# module.net
KiCad netlist of a schematic drawn in EAGLE
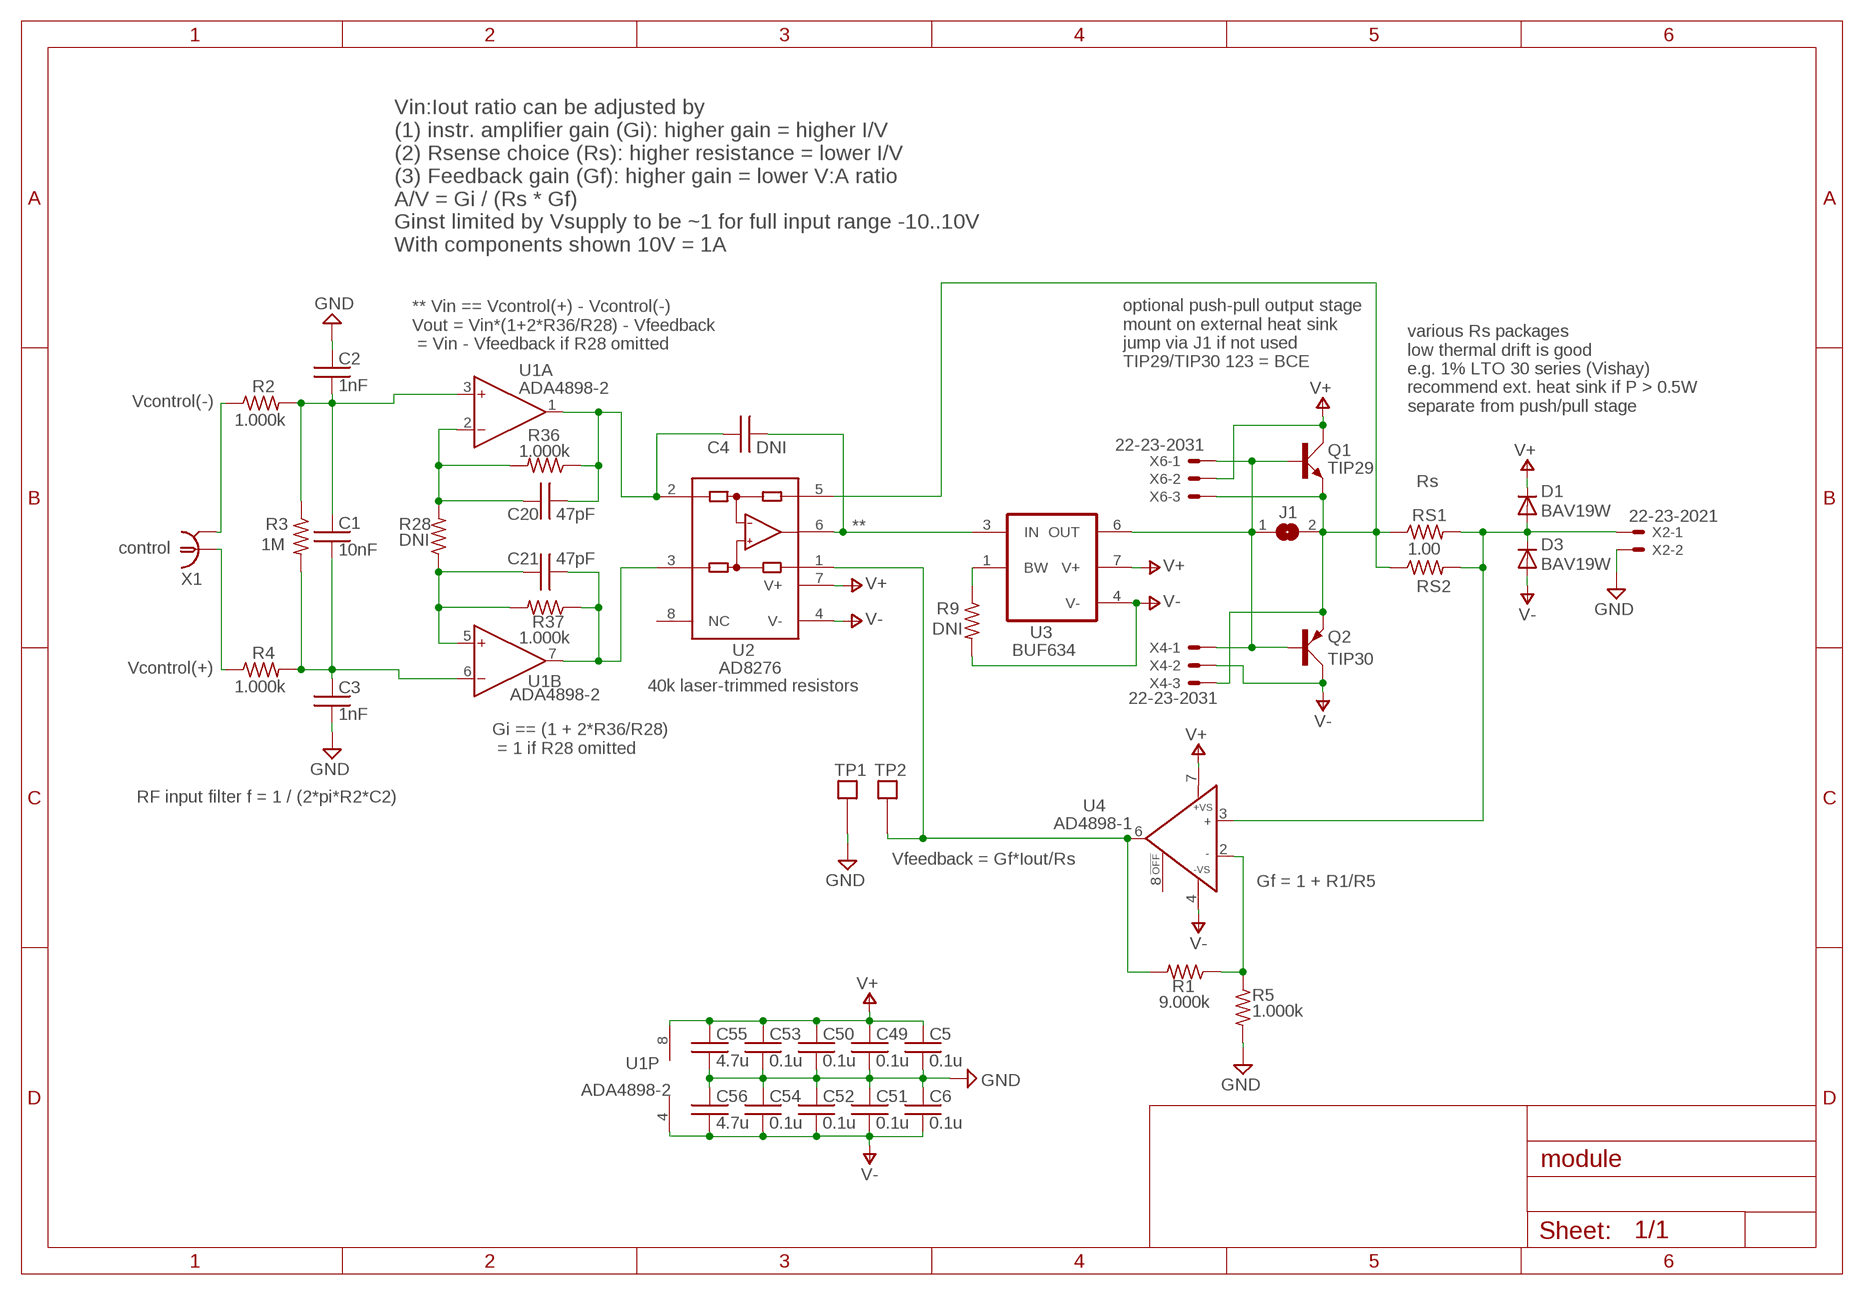
[diagram p0: schematic, sheet 1]

(export (version "E")
  (design (tool "Eeschema 10.0.6"))
  (components
    (comp (ref "C1")
      (value "10nF")
      (footprint "eagle-import:0603")
      (libsource (lib "eagle-import") (part "C0603"))
    )
    (comp (ref "C2")
      (value "1nF")
      (footprint "eagle-import:0603")
      (libsource (lib "eagle-import") (part "C0603"))
    )
    (comp (ref "C3")
      (value "1nF")
      (footprint "eagle-import:0603")
      (libsource (lib "eagle-import") (part "C0603"))
    )
    (comp (ref "C4")
      (value "DNI")
      (footprint "eagle-import:0603")
      (libsource (lib "eagle-import") (part "C0603"))
    )
    (comp (ref "C5")
      (value "0.1u")
      (footprint "eagle-import:0603")
      (libsource (lib "eagle-import") (part "C0603"))
    )
    (comp (ref "C6")
      (value "0.1u")
      (footprint "eagle-import:0603")
      (libsource (lib "eagle-import") (part "C0603"))
    )
    (comp (ref "C20")
      (value "47pF")
      (footprint "eagle-import:0603")
      (libsource (lib "eagle-import") (part "C0603"))
    )
    (comp (ref "C21")
      (value "47pF")
      (footprint "eagle-import:0603")
      (libsource (lib "eagle-import") (part "C0603"))
    )
    (comp (ref "C49")
      (value "0.1u")
      (footprint "eagle-import:0603")
      (libsource (lib "eagle-import") (part "C0603"))
    )
    (comp (ref "C50")
      (value "0.1u")
      (footprint "eagle-import:0603")
      (libsource (lib "eagle-import") (part "C0603"))
    )
    (comp (ref "C51")
      (value "0.1u")
      (footprint "eagle-import:0603")
      (libsource (lib "eagle-import") (part "C0603"))
    )
    (comp (ref "C52")
      (value "0.1u")
      (footprint "eagle-import:0603")
      (libsource (lib "eagle-import") (part "C0603"))
    )
    (comp (ref "C53")
      (value "0.1u")
      (footprint "eagle-import:0603")
      (libsource (lib "eagle-import") (part "C0603"))
    )
    (comp (ref "C54")
      (value "0.1u")
      (footprint "eagle-import:0603")
      (libsource (lib "eagle-import") (part "C0603"))
    )
    (comp (ref "C55")
      (value "4.7u")
      (footprint "eagle-import:0603")
      (libsource (lib "eagle-import") (part "C0603"))
    )
    (comp (ref "C56")
      (value "4.7u")
      (footprint "eagle-import:0603")
      (libsource (lib "eagle-import") (part "C0603"))
    )
    (comp (ref "D1")
      (value "BAV19W")
      (footprint "eagle-import:SOD123")
      (libsource (lib "eagle-import") (part "DIODE-SOD123"))
    )
    (comp (ref "D3")
      (value "BAV19W")
      (footprint "eagle-import:SOD123")
      (libsource (lib "eagle-import") (part "DIODE-SOD123"))
    )
    (comp (ref "J1") (value "SJ") (footprint "eagle-import:SJ") (libsource (lib "eagle-import") (part "SJ")))
    (comp (ref "Q1")
      (value "TIP29")
      (footprint "eagle-import:TO220AV")
      (libsource (lib "eagle-import") (part "TIP41C"))
    )
    (comp (ref "Q2")
      (value "TIP30")
      (footprint "eagle-import:TO220AV")
      (libsource (lib "eagle-import") (part "TIP42C"))
    )
    (comp (ref "R1")
      (value "9.000k")
      (footprint "eagle-import:0603")
      (libsource (lib "eagle-import") (part "R0603"))
    )
    (comp (ref "R2")
      (value "1.000k")
      (footprint "eagle-import:0603")
      (libsource (lib "eagle-import") (part "R0603"))
    )
    (comp (ref "R3")
      (value "1M")
      (footprint "eagle-import:0603")
      (libsource (lib "eagle-import") (part "R0603"))
    )
    (comp (ref "R4")
      (value "1.000k")
      (footprint "eagle-import:0603")
      (libsource (lib "eagle-import") (part "R0603"))
    )
    (comp (ref "R5")
      (value "1.000k")
      (footprint "eagle-import:0603")
      (libsource (lib "eagle-import") (part "R0603"))
    )
    (comp (ref "R9")
      (value "DNI")
      (footprint "eagle-import:0603")
      (libsource (lib "eagle-import") (part "R0603"))
    )
    (comp (ref "R28")
      (value "DNI")
      (footprint "eagle-import:0603")
      (libsource (lib "eagle-import") (part "R0603"))
    )
    (comp (ref "R36")
      (value "1.000k")
      (footprint "eagle-import:0603")
      (libsource (lib "eagle-import") (part "R0603"))
    )
    (comp (ref "R37")
      (value "1.000k")
      (footprint "eagle-import:0603")
      (libsource (lib "eagle-import") (part "R0603"))
    )
    (comp (ref "RS1")
      (value "1.00")
      (footprint "eagle-import:LTO30")
      (libsource (lib "eagle-import") (part "LT030"))
    )
    (comp (ref "RS2")
      (value "DNI")
      (footprint "eagle-import:2512")
      (libsource (lib "eagle-import") (part "RESISTOR2512"))
    )
    (comp (ref "TP1")
      (value "TESTPOINT")
      (footprint "eagle-import:TESTPOINT")
      (libsource (lib "eagle-import") (part "TESTPOINT"))
    )
    (comp (ref "TP2")
      (value "TESTPOINT")
      (footprint "eagle-import:TESTPOINT")
      (libsource (lib "eagle-import") (part "TESTPOINT"))
    )
    (comp (ref "U1")
      (value "ADA4898-2")
      (footprint "eagle-import:SO8")
      (fields (field (name "MF") "ALTERA CORPORATION") (field (name "MPN") "AD8542ARZ-REEL"))
      (libsource (lib "eagle-import") (part "ADA4898-2R"))
    )
    (comp (ref "U2")
      (value "AD8276")
      (footprint "eagle-import:SO8")
      (libsource (lib "eagle-import") (part "AD8276"))
    )
    (comp (ref "U3")
      (value "BUF634")
      (footprint "eagle-import:SO8")
      (libsource (lib "eagle-import") (part "BUF634"))
    )
    (comp (ref "U4")
      (value "AD4898-1")
      (footprint "eagle-import:SO8")
      (fields (field (name "MF") "ANALOG DEVICES") (field (name "MPN") "AD744JR"))
      (libsource (lib "eagle-import") (part "ADA4898-1R"))
    )
    (comp (ref "X1")
      (value "1-227161-0")
      (footprint "eagle-import:AMP_227161")
      (fields (field (name "MF") "TYCO ELECTRONICS") (field (name "MPN") "1-227161"))
      (libsource (lib "eagle-import") (part "?2271611--0"))
    )
    (comp (ref "X2")
      (value "22-23-2021")
      (footprint "eagle-import:22-23-2021")
      (fields (field (name "MF") "MOLEX"))
      (libsource (lib "eagle-import") (part "22-23-2021"))
    )
    (comp (ref "X4")
      (value "22-23-2031")
      (footprint "eagle-import:22-23-2031")
      (fields (field (name "MF") "MOLEX"))
      (libsource (lib "eagle-import") (part "22-23-2031"))
    )
    (comp (ref "X6")
      (value "22-23-2031")
      (footprint "eagle-import:22-23-2031")
      (fields (field (name "MF") "MOLEX"))
      (libsource (lib "eagle-import") (part "22-23-2031"))
    )
  )
  (nets
    (net (code "1") (name "GND") (class "Default")
      (node (ref "C2") (pin "1") (pinfunction "1_1") (pintype "passive"))
      (node (ref "C3") (pin "2") (pinfunction "2_2") (pintype "passive"))
      (node (ref "C49") (pin "2") (pinfunction "2_2") (pintype "passive"))
      (node (ref "C5") (pin "2") (pinfunction "2_2") (pintype "passive"))
      (node (ref "C50") (pin "2") (pinfunction "2_2") (pintype "passive"))
      (node (ref "C51") (pin "1") (pinfunction "1_1") (pintype "passive"))
      (node (ref "C52") (pin "1") (pinfunction "1_1") (pintype "passive"))
      (node (ref "C53") (pin "2") (pinfunction "2_2") (pintype "passive"))
      (node (ref "C54") (pin "1") (pinfunction "1_1") (pintype "passive"))
      (node (ref "C55") (pin "2") (pinfunction "2_2") (pintype "passive"))
      (node (ref "C56") (pin "1") (pinfunction "1_1") (pintype "passive"))
      (node (ref "C6") (pin "1") (pinfunction "1_1") (pintype "passive"))
      (node (ref "R5") (pin "2") (pinfunction "2_2") (pintype "passive"))
      (node (ref "TP1") (pin "P$1") (pinfunction "P$1_P$1") (pintype "bidirectional"))
      (node (ref "X2") (pin "2") (pinfunction "S_2") (pintype "passive"))
    )
    (net (code "2") (name "Net-(R2-Pad1)") (class "Default")
      (node (ref "R2") (pin "1") (pinfunction "1_1") (pintype "passive"))
      (node (ref "X1") (pin "2") (pinfunction "2_2") (pintype "passive"))
    )
    (net (code "3") (name "Net-(R4-Pad1)") (class "Default")
      (node (ref "R4") (pin "1") (pinfunction "1_1") (pintype "passive"))
      (node (ref "X1") (pin "1") (pinfunction "1_1") (pintype "passive"))
    )
    (net (code "4") (name "Net-(RS1-1)") (class "Default")
      (node (ref "J1") (pin "2") (pinfunction "2_2") (pintype "passive"))
      (node (ref "Q1") (pin "E") (pinfunction "E_E") (pintype "passive"))
      (node (ref "Q2") (pin "E") (pinfunction "E_E") (pintype "passive"))
      (node (ref "RS1") (pin "P$1") (pinfunction "1_P$1") (pintype "passive"))
      (node (ref "RS2") (pin "1") (pinfunction "1_1") (pintype "passive"))
      (node (ref "U2") (pin "5") (pinfunction "SENSE_5") (pintype "passive"))
      (node (ref "X4") (pin "3") (pinfunction "S_3") (pintype "passive"))
      (node (ref "X6") (pin "3") (pinfunction "S_3") (pintype "passive"))
    )
    (net (code "5") (name "Net-(RS1-2)") (class "Default")
      (node (ref "D1") (pin "A") (pinfunction "A_A") (pintype "passive"))
      (node (ref "D3") (pin "C") (pinfunction "C_C") (pintype "passive"))
      (node (ref "RS1") (pin "P$2") (pinfunction "2_P$2") (pintype "passive"))
      (node (ref "RS2") (pin "2") (pinfunction "2_2") (pintype "passive"))
      (node (ref "U4") (pin "3") (pinfunction "IN+_3") (pintype "input"))
      (node (ref "X2") (pin "1") (pinfunction "S_1") (pintype "passive"))
    )
    (net (code "6") (name "Net-(U1A-IN+)") (class "Default")
      (node (ref "C1") (pin "1") (pinfunction "1_1") (pintype "passive"))
      (node (ref "C2") (pin "2") (pinfunction "2_2") (pintype "passive"))
      (node (ref "R2") (pin "2") (pinfunction "2_2") (pintype "passive"))
      (node (ref "R3") (pin "1") (pinfunction "1_1") (pintype "passive"))
      (node (ref "U1") (pin "3") (pinfunction "IN+_3") (pintype "input"))
    )
    (net (code "7") (name "Net-(U1A-IN-)") (class "Default")
      (node (ref "C20") (pin "1") (pinfunction "1_1") (pintype "passive"))
      (node (ref "R28") (pin "2") (pinfunction "2_2") (pintype "passive"))
      (node (ref "R36") (pin "2") (pinfunction "2_2") (pintype "passive"))
      (node (ref "U1") (pin "2") (pinfunction "IN-_2") (pintype "input"))
    )
    (net (code "8") (name "Net-(U1A-OUT)") (class "Default")
      (node (ref "C20") (pin "2") (pinfunction "2_2") (pintype "passive"))
      (node (ref "C4") (pin "1") (pinfunction "1_1") (pintype "passive"))
      (node (ref "R36") (pin "1") (pinfunction "1_1") (pintype "passive"))
      (node (ref "U1") (pin "1") (pinfunction "OUT_1") (pintype "output"))
      (node (ref "U2") (pin "2") (pinfunction "-IN_2") (pintype "input"))
    )
    (net (code "9") (name "Net-(U1B-IN+)") (class "Default")
      (node (ref "C21") (pin "1") (pinfunction "1_1") (pintype "passive"))
      (node (ref "R28") (pin "1") (pinfunction "1_1") (pintype "passive"))
      (node (ref "R37") (pin "2") (pinfunction "2_2") (pintype "passive"))
      (node (ref "U1") (pin "5") (pinfunction "IN+_5") (pintype "input"))
    )
    (net (code "10") (name "Net-(U1B-IN-)") (class "Default")
      (node (ref "C1") (pin "2") (pinfunction "2_2") (pintype "passive"))
      (node (ref "C3") (pin "1") (pinfunction "1_1") (pintype "passive"))
      (node (ref "R3") (pin "2") (pinfunction "2_2") (pintype "passive"))
      (node (ref "R4") (pin "2") (pinfunction "2_2") (pintype "passive"))
      (node (ref "U1") (pin "6") (pinfunction "IN-_6") (pintype "input"))
    )
    (net (code "11") (name "Net-(U1B-OUT)") (class "Default")
      (node (ref "C21") (pin "2") (pinfunction "2_2") (pintype "passive"))
      (node (ref "R37") (pin "1") (pinfunction "1_1") (pintype "passive"))
      (node (ref "U1") (pin "7") (pinfunction "OUT_7") (pintype "output"))
      (node (ref "U2") (pin "3") (pinfunction "+IN_3") (pintype "input"))
    )
    (net (code "12") (name "Net-(U2-OUT)") (class "Default")
      (node (ref "C4") (pin "2") (pinfunction "2_2") (pintype "passive"))
      (node (ref "U2") (pin "6") (pinfunction "OUT_6") (pintype "output"))
      (node (ref "U3") (pin "3") (pinfunction "IN_3") (pintype "input"))
    )
    (net (code "13") (name "Net-(U2-REF)") (class "Default")
      (node (ref "R1") (pin "2") (pinfunction "2_2") (pintype "passive"))
      (node (ref "TP2") (pin "P$1") (pinfunction "P$1_P$1") (pintype "bidirectional"))
      (node (ref "U2") (pin "1") (pinfunction "REF_1") (pintype "passive"))
      (node (ref "U4") (pin "6") (pinfunction "OUT_6") (pintype "output"))
    )
    (net (code "14") (name "Net-(U3-BW)") (class "Default")
      (node (ref "R9") (pin "1") (pinfunction "1_1") (pintype "passive"))
      (node (ref "U3") (pin "1") (pinfunction "BW_1") (pintype "passive"))
    )
    (net (code "15") (name "Net-(U3-OUT)") (class "Default")
      (node (ref "J1") (pin "1") (pinfunction "1_1") (pintype "passive"))
      (node (ref "Q1") (pin "B") (pinfunction "B_B") (pintype "passive"))
      (node (ref "Q2") (pin "B") (pinfunction "B_B") (pintype "passive"))
      (node (ref "U3") (pin "6") (pinfunction "OUT_6") (pintype "output"))
      (node (ref "X4") (pin "1") (pinfunction "S_1") (pintype "passive"))
      (node (ref "X6") (pin "1") (pinfunction "S_1") (pintype "passive"))
    )
    (net (code "16") (name "Net-(U4-IN-)") (class "Default")
      (node (ref "R1") (pin "1") (pinfunction "1_1") (pintype "passive"))
      (node (ref "R5") (pin "1") (pinfunction "1_1") (pintype "passive"))
      (node (ref "U4") (pin "2") (pinfunction "IN-_2") (pintype "input"))
    )
    (net (code "17") (name "V+") (class "Default")
      (node (ref "C49") (pin "1") (pinfunction "1_1") (pintype "passive"))
      (node (ref "C5") (pin "1") (pinfunction "1_1") (pintype "passive"))
      (node (ref "C50") (pin "1") (pinfunction "1_1") (pintype "passive"))
      (node (ref "C53") (pin "1") (pinfunction "1_1") (pintype "passive"))
      (node (ref "C55") (pin "1") (pinfunction "1_1") (pintype "passive"))
      (node (ref "D1") (pin "C") (pinfunction "C_C") (pintype "passive"))
      (node (ref "Q1") (pin "C") (pinfunction "C_C") (pintype "passive"))
      (node (ref "U1") (pin "8") (pinfunction "V+_8") (pintype "power_in"))
      (node (ref "U2") (pin "7") (pinfunction "V+_7") (pintype "power_in"))
      (node (ref "U3") (pin "7") (pinfunction "V+_7") (pintype "power_in"))
      (node (ref "U4") (pin "7") (pinfunction "+VS_7") (pintype "input"))
      (node (ref "X6") (pin "2") (pinfunction "S_2") (pintype "passive"))
    )
    (net (code "18") (name "V-") (class "Default")
      (node (ref "C51") (pin "2") (pinfunction "2_2") (pintype "passive"))
      (node (ref "C52") (pin "2") (pinfunction "2_2") (pintype "passive"))
      (node (ref "C54") (pin "2") (pinfunction "2_2") (pintype "passive"))
      (node (ref "C56") (pin "2") (pinfunction "2_2") (pintype "passive"))
      (node (ref "C6") (pin "2") (pinfunction "2_2") (pintype "passive"))
      (node (ref "D3") (pin "A") (pinfunction "A_A") (pintype "passive"))
      (node (ref "Q2") (pin "C") (pinfunction "C_C") (pintype "passive"))
      (node (ref "R9") (pin "2") (pinfunction "2_2") (pintype "passive"))
      (node (ref "U1") (pin "4") (pinfunction "V-_4") (pintype "power_in"))
      (node (ref "U2") (pin "4") (pinfunction "V-_4") (pintype "power_in"))
      (node (ref "U3") (pin "4") (pinfunction "V-_4") (pintype "power_in"))
      (node (ref "U4") (pin "4") (pinfunction "-VS_4") (pintype "input"))
      (node (ref "X4") (pin "2") (pinfunction "S_2") (pintype "passive"))
    )
    (net (code "19") (name "unconnected-(U2-NC-Pad8)") (class "Default")
      (node (ref "U2") (pin "8") (pinfunction "NC_8") (pintype "no_connect"))
    )
    (net (code "20") (name "unconnected-(U4-OFF-Pad8)") (class "Default")
      (node (ref "U4") (pin "8") (pinfunction "OFF_8") (pintype "passive"))
    )
  )
)
